# quadstep-v020.net
KiCad netlist of a schematic drawn in EAGLE
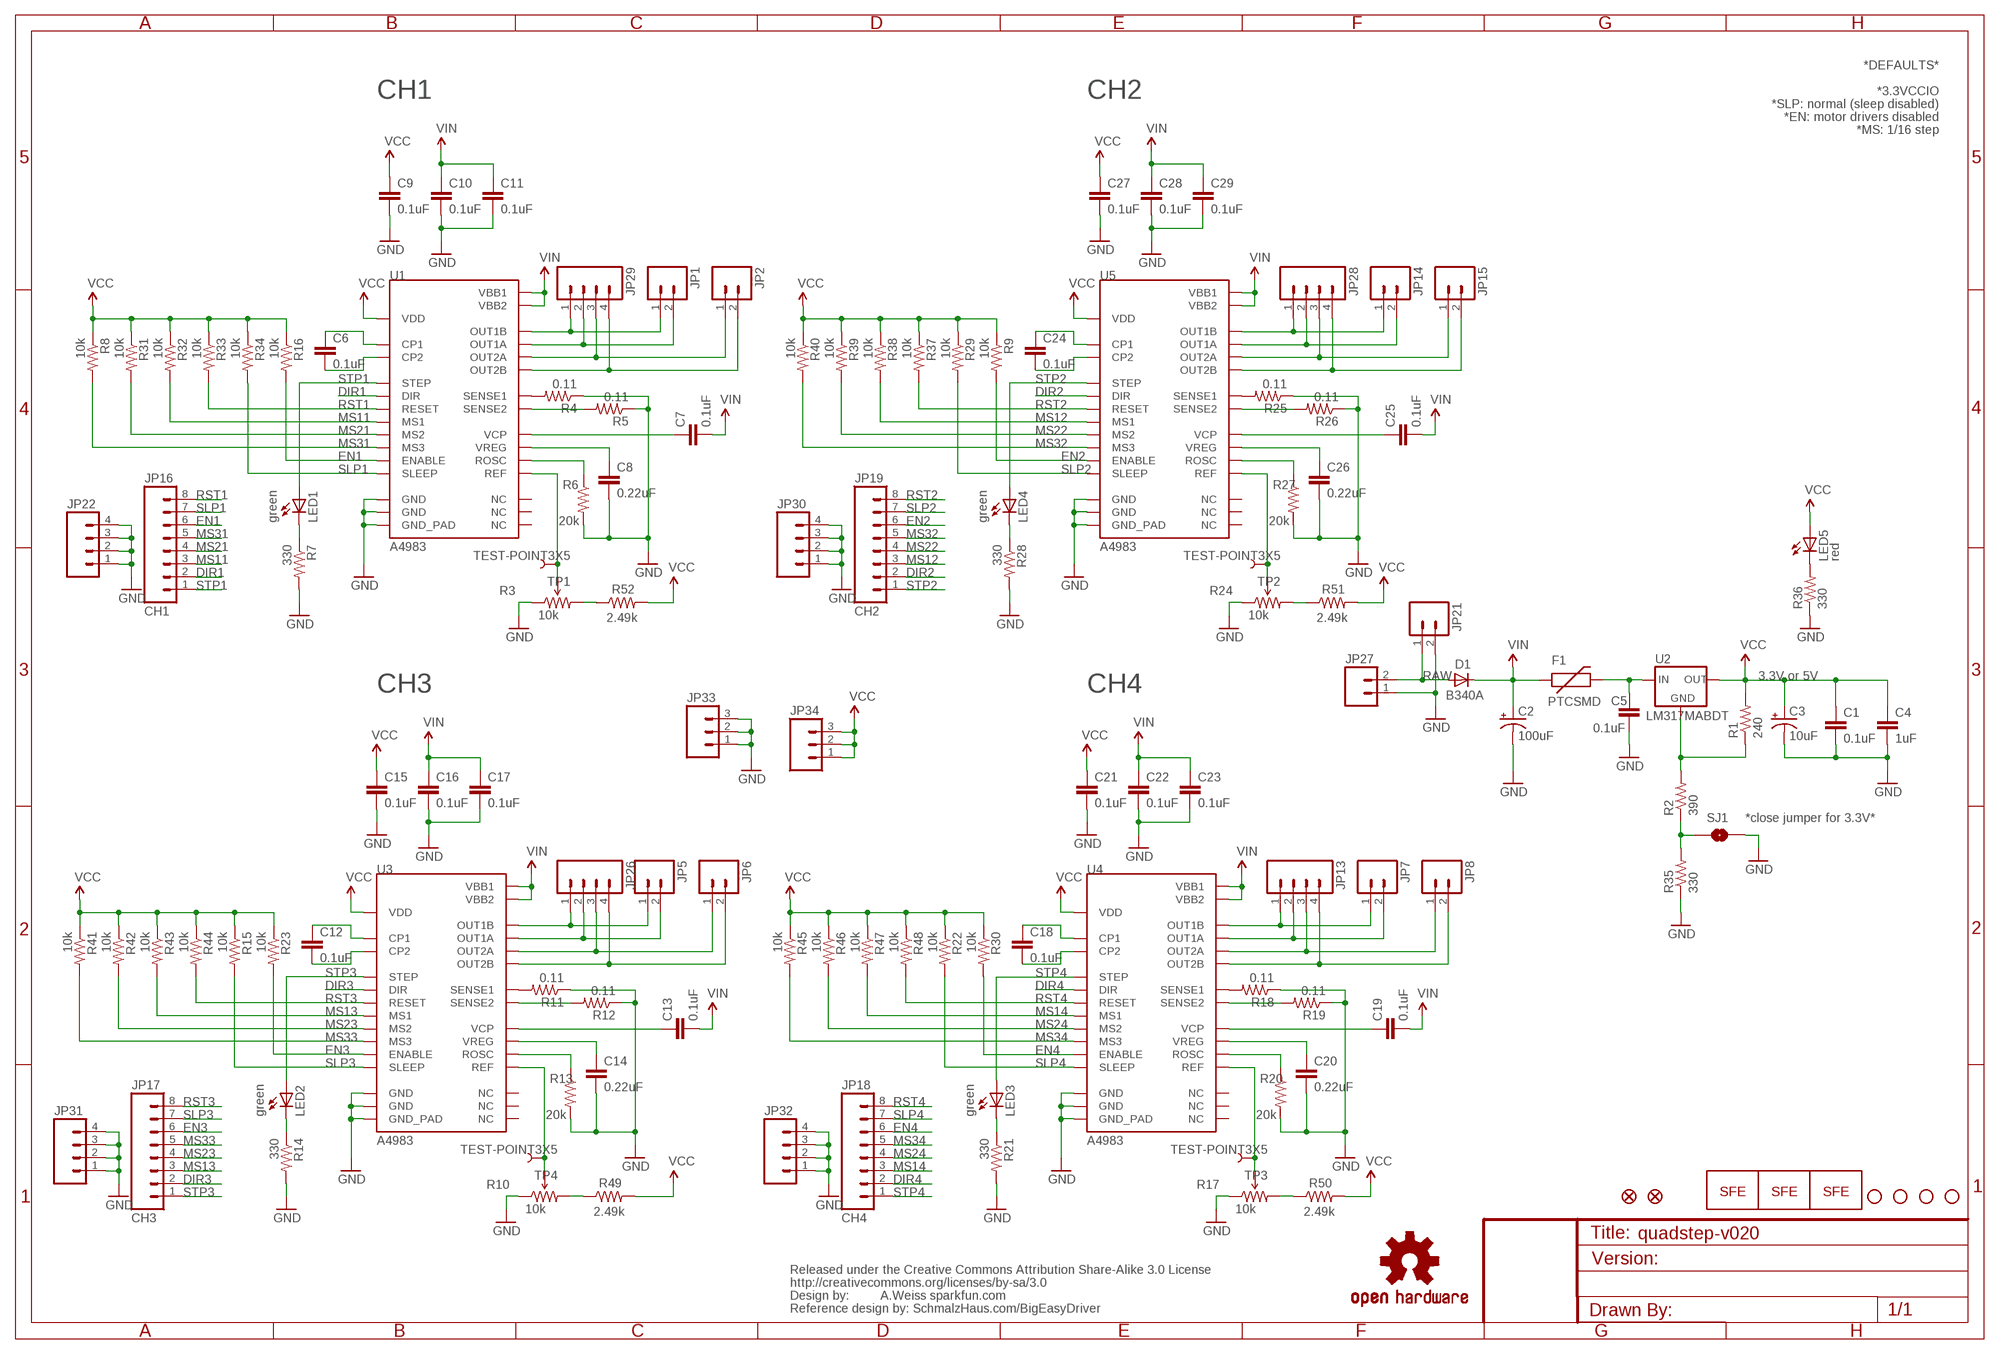
[diagram p0: schematic, sheet 1]

(export (version "E")
  (design (tool "Eeschema 10.0.6"))
  (components
    (comp (ref "C1")
      (value "0.1uF")
      (footprint "eagle-import:0402-CAP")
      (libsource (lib "eagle-import") (part "CAP0402-CAP"))
    )
    (comp (ref "C2")
      (value "100uF")
      (footprint "eagle-import:PANASONIC_G")
      (libsource (lib "eagle-import") (part "CAP_POLG"))
    )
    (comp (ref "C3")
      (value "10uF")
      (footprint "eagle-import:EIA3216")
      (libsource (lib "eagle-import") (part "CAP_POL1206"))
    )
    (comp (ref "C4")
      (value "1uF")
      (footprint "eagle-import:0805")
      (libsource (lib "eagle-import") (part "CAP0805"))
    )
    (comp (ref "C5")
      (value "0.1uF")
      (footprint "eagle-import:0402-CAP")
      (libsource (lib "eagle-import") (part "CAP0402-CAP"))
    )
    (comp (ref "C6")
      (value "0.1uF")
      (footprint "eagle-import:0402-CAP")
      (libsource (lib "eagle-import") (part "CAP0402-CAP"))
    )
    (comp (ref "C7")
      (value "0.1uF")
      (footprint "eagle-import:0402-CAP")
      (libsource (lib "eagle-import") (part "CAP0402-CAP"))
    )
    (comp (ref "C8")
      (value "0.22uF")
      (footprint "eagle-import:0402-CAP")
      (libsource (lib "eagle-import") (part "CAP0402-CAP"))
    )
    (comp (ref "C9")
      (value "0.1uF")
      (footprint "eagle-import:0402-CAP")
      (libsource (lib "eagle-import") (part "CAP0402-CAP"))
    )
    (comp (ref "C10")
      (value "0.1uF")
      (footprint "eagle-import:0402-CAP")
      (libsource (lib "eagle-import") (part "CAP0402-CAP"))
    )
    (comp (ref "C11")
      (value "0.1uF")
      (footprint "eagle-import:0402-CAP")
      (libsource (lib "eagle-import") (part "CAP0402-CAP"))
    )
    (comp (ref "C12")
      (value "0.1uF")
      (footprint "eagle-import:0402-CAP")
      (libsource (lib "eagle-import") (part "CAP0402-CAP"))
    )
    (comp (ref "C13")
      (value "0.1uF")
      (footprint "eagle-import:0402-CAP")
      (libsource (lib "eagle-import") (part "CAP0402-CAP"))
    )
    (comp (ref "C14")
      (value "0.22uF")
      (footprint "eagle-import:0402-CAP")
      (libsource (lib "eagle-import") (part "CAP0402-CAP"))
    )
    (comp (ref "C15")
      (value "0.1uF")
      (footprint "eagle-import:0402-CAP")
      (libsource (lib "eagle-import") (part "CAP0402-CAP"))
    )
    (comp (ref "C16")
      (value "0.1uF")
      (footprint "eagle-import:0402-CAP")
      (libsource (lib "eagle-import") (part "CAP0402-CAP"))
    )
    (comp (ref "C17")
      (value "0.1uF")
      (footprint "eagle-import:0402-CAP")
      (libsource (lib "eagle-import") (part "CAP0402-CAP"))
    )
    (comp (ref "C18")
      (value "0.1uF")
      (footprint "eagle-import:0402-CAP")
      (libsource (lib "eagle-import") (part "CAP0402-CAP"))
    )
    (comp (ref "C19")
      (value "0.1uF")
      (footprint "eagle-import:0402-CAP")
      (libsource (lib "eagle-import") (part "CAP0402-CAP"))
    )
    (comp (ref "C20")
      (value "0.22uF")
      (footprint "eagle-import:0402-CAP")
      (libsource (lib "eagle-import") (part "CAP0402-CAP"))
    )
    (comp (ref "C21")
      (value "0.1uF")
      (footprint "eagle-import:0402-CAP")
      (libsource (lib "eagle-import") (part "CAP0402-CAP"))
    )
    (comp (ref "C22")
      (value "0.1uF")
      (footprint "eagle-import:0402-CAP")
      (libsource (lib "eagle-import") (part "CAP0402-CAP"))
    )
    (comp (ref "C23")
      (value "0.1uF")
      (footprint "eagle-import:0402-CAP")
      (libsource (lib "eagle-import") (part "CAP0402-CAP"))
    )
    (comp (ref "C24")
      (value "0.1uF")
      (footprint "eagle-import:0402-CAP")
      (libsource (lib "eagle-import") (part "CAP0402-CAP"))
    )
    (comp (ref "C25")
      (value "0.1uF")
      (footprint "eagle-import:0402-CAP")
      (libsource (lib "eagle-import") (part "CAP0402-CAP"))
    )
    (comp (ref "C26")
      (value "0.22uF")
      (footprint "eagle-import:0402-CAP")
      (libsource (lib "eagle-import") (part "CAP0402-CAP"))
    )
    (comp (ref "C27")
      (value "0.1uF")
      (footprint "eagle-import:0402-CAP")
      (libsource (lib "eagle-import") (part "CAP0402-CAP"))
    )
    (comp (ref "C28")
      (value "0.1uF")
      (footprint "eagle-import:0402-CAP")
      (libsource (lib "eagle-import") (part "CAP0402-CAP"))
    )
    (comp (ref "C29")
      (value "0.1uF")
      (footprint "eagle-import:0402-CAP")
      (libsource (lib "eagle-import") (part "CAP0402-CAP"))
    )
    (comp (ref "CC_TEXT1")
      (value "CREATIVE_COMMONS")
      (footprint "eagle-import:CREATIVE_COMMONS")
      (libsource (lib "eagle-import") (part "CREATIVE_COMMONS"))
    )
    (comp (ref "D1")
      (value "B340A")
      (footprint "eagle-import:SMA-DIODE")
      (libsource (lib "eagle-import") (part "DIODESMA"))
    )
    (comp (ref "F1")
      (value "PTCSMD")
      (footprint "eagle-import:PTC-1206")
      (libsource (lib "eagle-import") (part "PTCSMD"))
    )
    (comp (ref "JP1")
      (value "M023.5MM_LOCK")
      (footprint "eagle-import:SCREWTERMINAL-3.5MM-2_LOCK")
      (libsource (lib "eagle-import") (part "M023.5MM_LOCK"))
    )
    (comp (ref "JP2")
      (value "M023.5MM_LOCK")
      (footprint "eagle-import:SCREWTERMINAL-3.5MM-2_LOCK")
      (libsource (lib "eagle-import") (part "M023.5MM_LOCK"))
    )
    (comp (ref "JP5")
      (value "M023.5MM_LOCK")
      (footprint "eagle-import:SCREWTERMINAL-3.5MM-2_LOCK")
      (libsource (lib "eagle-import") (part "M023.5MM_LOCK"))
    )
    (comp (ref "JP6")
      (value "M023.5MM_LOCK")
      (footprint "eagle-import:SCREWTERMINAL-3.5MM-2_LOCK")
      (libsource (lib "eagle-import") (part "M023.5MM_LOCK"))
    )
    (comp (ref "JP7")
      (value "M023.5MM_LOCK")
      (footprint "eagle-import:SCREWTERMINAL-3.5MM-2_LOCK")
      (libsource (lib "eagle-import") (part "M023.5MM_LOCK"))
    )
    (comp (ref "JP8")
      (value "M023.5MM_LOCK")
      (footprint "eagle-import:SCREWTERMINAL-3.5MM-2_LOCK")
      (libsource (lib "eagle-import") (part "M023.5MM_LOCK"))
    )
    (comp (ref "JP9")
      (value "STAND-OFF")
      (footprint "eagle-import:STAND-OFF")
      (libsource (lib "eagle-import") (part "STAND-OFF"))
    )
    (comp (ref "JP10")
      (value "STAND-OFF")
      (footprint "eagle-import:STAND-OFF")
      (libsource (lib "eagle-import") (part "STAND-OFF"))
    )
    (comp (ref "JP11")
      (value "STAND-OFF")
      (footprint "eagle-import:STAND-OFF")
      (libsource (lib "eagle-import") (part "STAND-OFF"))
    )
    (comp (ref "JP12")
      (value "STAND-OFF")
      (footprint "eagle-import:STAND-OFF")
      (libsource (lib "eagle-import") (part "STAND-OFF"))
    )
    (comp (ref "JP13")
      (value "M04PTH")
      (footprint "eagle-import:1X04")
      (libsource (lib "eagle-import") (part "M04PTH"))
    )
    (comp (ref "JP14")
      (value "M023.5MM_LOCK")
      (footprint "eagle-import:SCREWTERMINAL-3.5MM-2_LOCK")
      (libsource (lib "eagle-import") (part "M023.5MM_LOCK"))
    )
    (comp (ref "JP15")
      (value "M023.5MM_LOCK")
      (footprint "eagle-import:SCREWTERMINAL-3.5MM-2_LOCK")
      (libsource (lib "eagle-import") (part "M023.5MM_LOCK"))
    )
    (comp (ref "JP16")
      (value "CH1")
      (footprint "eagle-import:1X08")
      (libsource (lib "eagle-import") (part "M08"))
    )
    (comp (ref "JP17")
      (value "CH3")
      (footprint "eagle-import:1X08")
      (libsource (lib "eagle-import") (part "M08"))
    )
    (comp (ref "JP18")
      (value "CH4")
      (footprint "eagle-import:1X08")
      (libsource (lib "eagle-import") (part "M08"))
    )
    (comp (ref "JP19")
      (value "CH2")
      (footprint "eagle-import:1X08")
      (libsource (lib "eagle-import") (part "M08"))
    )
    (comp (ref "JP20")
      (value "LOGO-SFENEW")
      (footprint "eagle-import:SFE-NEW-WEBLOGO")
      (libsource (lib "eagle-import") (part "LOGO-SFENEW"))
    )
    (comp (ref "JP21")
      (value "M025MM")
      (footprint "eagle-import:SCREWTERMINAL-5MM-2")
      (libsource (lib "eagle-import") (part "M025MM"))
    )
    (comp (ref "JP22")
      (value "M04PTH")
      (footprint "eagle-import:1X04")
      (libsource (lib "eagle-import") (part "M04PTH"))
    )
    (comp (ref "JP23")
      (value "LOGO-SFESK")
      (footprint "eagle-import:SFE-LOGO-FLAME")
      (libsource (lib "eagle-import") (part "LOGO-SFESK"))
    )
    (comp (ref "JP24")
      (value "FIDUCIAL1X2")
      (footprint "eagle-import:FIDUCIAL-1X2")
      (libsource (lib "eagle-import") (part "FIDUCIAL1X2"))
    )
    (comp (ref "JP25")
      (value "FIDUCIAL1X2")
      (footprint "eagle-import:FIDUCIAL-1X2")
      (libsource (lib "eagle-import") (part "FIDUCIAL1X2"))
    )
    (comp (ref "JP26")
      (value "M04PTH")
      (footprint "eagle-import:1X04")
      (libsource (lib "eagle-import") (part "M04PTH"))
    )
    (comp (ref "JP27")
      (value "M02PTH")
      (footprint "eagle-import:1X02")
      (libsource (lib "eagle-import") (part "SparkFun-Connectors_M02PTH"))
    )
    (comp (ref "JP28")
      (value "M04PTH")
      (footprint "eagle-import:1X04")
      (libsource (lib "eagle-import") (part "M04PTH"))
    )
    (comp (ref "JP29")
      (value "M04PTH")
      (footprint "eagle-import:1X04")
      (libsource (lib "eagle-import") (part "M04PTH"))
    )
    (comp (ref "JP30")
      (value "M04PTH")
      (footprint "eagle-import:1X04")
      (libsource (lib "eagle-import") (part "M04PTH"))
    )
    (comp (ref "JP31")
      (value "M04PTH")
      (footprint "eagle-import:1X04")
      (libsource (lib "eagle-import") (part "M04PTH"))
    )
    (comp (ref "JP32")
      (value "M04PTH")
      (footprint "eagle-import:1X04")
      (libsource (lib "eagle-import") (part "M04PTH"))
    )
    (comp (ref "JP33")
      (value "M03PTH")
      (footprint "eagle-import:1X03")
      (libsource (lib "eagle-import") (part "M03PTH"))
    )
    (comp (ref "JP34")
      (value "M03PTH")
      (footprint "eagle-import:1X03")
      (libsource (lib "eagle-import") (part "M03PTH"))
    )
    (comp (ref "LED1")
      (value "green")
      (footprint "eagle-import:LED-0603")
      (libsource (lib "eagle-import") (part "LED0603"))
    )
    (comp (ref "LED2")
      (value "green")
      (footprint "eagle-import:LED-0603")
      (libsource (lib "eagle-import") (part "LED0603"))
    )
    (comp (ref "LED3")
      (value "green")
      (footprint "eagle-import:LED-0603")
      (libsource (lib "eagle-import") (part "LED0603"))
    )
    (comp (ref "LED4")
      (value "green")
      (footprint "eagle-import:LED-0603")
      (libsource (lib "eagle-import") (part "LED0603"))
    )
    (comp (ref "LED5")
      (value "red")
      (footprint "eagle-import:LED-0603")
      (libsource (lib "eagle-import") (part "LED0603"))
    )
    (comp (ref "LOGO1")
      (value "LOGO-SFENW2")
      (footprint "eagle-import:SFE-NEW-WEB")
      (libsource (lib "eagle-import") (part "SparkFun-Aesthetics_LOGO-SFENW2"))
    )
    (comp (ref "R1")
      (value "240")
      (footprint "eagle-import:0402-RES")
      (libsource (lib "eagle-import") (part "RESISTOR0402-RES"))
    )
    (comp (ref "R2")
      (value "390")
      (footprint "eagle-import:0402-RES")
      (libsource (lib "eagle-import") (part "RESISTOR0402-RES"))
    )
    (comp (ref "R3")
      (value "10k")
      (footprint "eagle-import:TRIMPOT-3MM")
      (libsource (lib "eagle-import") (part "TRIMPOTSMD"))
    )
    (comp (ref "R4")
      (value "0.11")
      (footprint "eagle-import:R2010")
      (libsource (lib "eagle-import") (part "RESISTOR2010"))
    )
    (comp (ref "R5")
      (value "0.11")
      (footprint "eagle-import:R2010")
      (libsource (lib "eagle-import") (part "RESISTOR2010"))
    )
    (comp (ref "R6")
      (value "20k")
      (footprint "eagle-import:0402-RES")
      (libsource (lib "eagle-import") (part "RESISTOR0402-RES"))
    )
    (comp (ref "R7")
      (value "330")
      (footprint "eagle-import:0402-RES")
      (libsource (lib "eagle-import") (part "RESISTOR0402-RES"))
    )
    (comp (ref "R8")
      (value "10k")
      (footprint "eagle-import:0402-RES")
      (libsource (lib "eagle-import") (part "RESISTOR0402-RES"))
    )
    (comp (ref "R9")
      (value "10k")
      (footprint "eagle-import:0402-RES")
      (libsource (lib "eagle-import") (part "RESISTOR0402-RES"))
    )
    (comp (ref "R10")
      (value "10k")
      (footprint "eagle-import:TRIMPOT-3MM")
      (libsource (lib "eagle-import") (part "TRIMPOTSMD"))
    )
    (comp (ref "R11")
      (value "0.11")
      (footprint "eagle-import:R2010")
      (libsource (lib "eagle-import") (part "RESISTOR2010"))
    )
    (comp (ref "R12")
      (value "0.11")
      (footprint "eagle-import:R2010")
      (libsource (lib "eagle-import") (part "RESISTOR2010"))
    )
    (comp (ref "R13")
      (value "20k")
      (footprint "eagle-import:0402-RES")
      (libsource (lib "eagle-import") (part "RESISTOR0402-RES"))
    )
    (comp (ref "R14")
      (value "330")
      (footprint "eagle-import:0402-RES")
      (libsource (lib "eagle-import") (part "RESISTOR0402-RES"))
    )
    (comp (ref "R15")
      (value "10k")
      (footprint "eagle-import:0402-RES")
      (libsource (lib "eagle-import") (part "RESISTOR0402-RES"))
    )
    (comp (ref "R16")
      (value "10k")
      (footprint "eagle-import:0402-RES")
      (libsource (lib "eagle-import") (part "RESISTOR0402-RES"))
    )
    (comp (ref "R17")
      (value "10k")
      (footprint "eagle-import:TRIMPOT-3MM")
      (libsource (lib "eagle-import") (part "TRIMPOTSMD"))
    )
    (comp (ref "R18")
      (value "0.11")
      (footprint "eagle-import:R2010")
      (libsource (lib "eagle-import") (part "RESISTOR2010"))
    )
    (comp (ref "R19")
      (value "0.11")
      (footprint "eagle-import:R2010")
      (libsource (lib "eagle-import") (part "RESISTOR2010"))
    )
    (comp (ref "R20")
      (value "20k")
      (footprint "eagle-import:0402-RES")
      (libsource (lib "eagle-import") (part "RESISTOR0402-RES"))
    )
    (comp (ref "R21")
      (value "330")
      (footprint "eagle-import:0402-RES")
      (libsource (lib "eagle-import") (part "RESISTOR0402-RES"))
    )
    (comp (ref "R22")
      (value "10k")
      (footprint "eagle-import:0402-RES")
      (libsource (lib "eagle-import") (part "RESISTOR0402-RES"))
    )
    (comp (ref "R23")
      (value "10k")
      (footprint "eagle-import:0402-RES")
      (libsource (lib "eagle-import") (part "RESISTOR0402-RES"))
    )
    (comp (ref "R24")
      (value "10k")
      (footprint "eagle-import:TRIMPOT-3MM")
      (libsource (lib "eagle-import") (part "TRIMPOTSMD"))
    )
    (comp (ref "R25")
      (value "0.11")
      (footprint "eagle-import:R2010")
      (libsource (lib "eagle-import") (part "RESISTOR2010"))
    )
    (comp (ref "R26")
      (value "0.11")
      (footprint "eagle-import:R2010")
      (libsource (lib "eagle-import") (part "RESISTOR2010"))
    )
    (comp (ref "R27")
      (value "20k")
      (footprint "eagle-import:0402-RES")
      (libsource (lib "eagle-import") (part "RESISTOR0402-RES"))
    )
    (comp (ref "R28")
      (value "330")
      (footprint "eagle-import:0402-RES")
      (libsource (lib "eagle-import") (part "RESISTOR0402-RES"))
    )
    (comp (ref "R29")
      (value "10k")
      (footprint "eagle-import:0402-RES")
      (libsource (lib "eagle-import") (part "RESISTOR0402-RES"))
    )
    (comp (ref "R30")
      (value "10k")
      (footprint "eagle-import:0402-RES")
      (libsource (lib "eagle-import") (part "RESISTOR0402-RES"))
    )
    (comp (ref "R31")
      (value "10k")
      (footprint "eagle-import:0402-RES")
      (libsource (lib "eagle-import") (part "RESISTOR0402-RES"))
    )
    (comp (ref "R32")
      (value "10k")
      (footprint "eagle-import:0402-RES")
      (libsource (lib "eagle-import") (part "RESISTOR0402-RES"))
    )
    (comp (ref "R33")
      (value "10k")
      (footprint "eagle-import:0402-RES")
      (libsource (lib "eagle-import") (part "RESISTOR0402-RES"))
    )
    (comp (ref "R34")
      (value "10k")
      (footprint "eagle-import:0402-RES")
      (libsource (lib "eagle-import") (part "RESISTOR0402-RES"))
    )
    (comp (ref "R35")
      (value "330")
      (footprint "eagle-import:0402-RES")
      (libsource (lib "eagle-import") (part "RESISTOR0402-RES"))
    )
    (comp (ref "R36")
      (value "330")
      (footprint "eagle-import:0402-RES")
      (libsource (lib "eagle-import") (part "RESISTOR0402-RES"))
    )
    (comp (ref "R37")
      (value "10k")
      (footprint "eagle-import:0402-RES")
      (libsource (lib "eagle-import") (part "RESISTOR0402-RES"))
    )
    (comp (ref "R38")
      (value "10k")
      (footprint "eagle-import:0402-RES")
      (libsource (lib "eagle-import") (part "RESISTOR0402-RES"))
    )
    (comp (ref "R39")
      (value "10k")
      (footprint "eagle-import:0402-RES")
      (libsource (lib "eagle-import") (part "RESISTOR0402-RES"))
    )
    (comp (ref "R40")
      (value "10k")
      (footprint "eagle-import:0402-RES")
      (libsource (lib "eagle-import") (part "RESISTOR0402-RES"))
    )
    (comp (ref "R41")
      (value "10k")
      (footprint "eagle-import:0402-RES")
      (libsource (lib "eagle-import") (part "RESISTOR0402-RES"))
    )
    (comp (ref "R42")
      (value "10k")
      (footprint "eagle-import:0402-RES")
      (libsource (lib "eagle-import") (part "RESISTOR0402-RES"))
    )
    (comp (ref "R43")
      (value "10k")
      (footprint "eagle-import:0402-RES")
      (libsource (lib "eagle-import") (part "RESISTOR0402-RES"))
    )
    (comp (ref "R44")
      (value "10k")
      (footprint "eagle-import:0402-RES")
      (libsource (lib "eagle-import") (part "RESISTOR0402-RES"))
    )
    (comp (ref "R45")
      (value "10k")
      (footprint "eagle-import:0402-RES")
      (libsource (lib "eagle-import") (part "RESISTOR0402-RES"))
    )
    (comp (ref "R46")
      (value "10k")
      (footprint "eagle-import:0402-RES")
      (libsource (lib "eagle-import") (part "RESISTOR0402-RES"))
    )
    (comp (ref "R47")
      (value "10k")
      (footprint "eagle-import:0402-RES")
      (libsource (lib "eagle-import") (part "RESISTOR0402-RES"))
    )
    (comp (ref "R48")
      (value "10k")
      (footprint "eagle-import:0402-RES")
      (libsource (lib "eagle-import") (part "RESISTOR0402-RES"))
    )
    (comp (ref "R49")
      (value "2.49k")
      (footprint "eagle-import:0402-RES")
      (libsource (lib "eagle-import") (part "RESISTOR0402-RES"))
    )
    (comp (ref "R50")
      (value "2.49k")
      (footprint "eagle-import:0402-RES")
      (libsource (lib "eagle-import") (part "RESISTOR0402-RES"))
    )
    (comp (ref "R51")
      (value "2.49k")
      (footprint "eagle-import:0402-RES")
      (libsource (lib "eagle-import") (part "RESISTOR0402-RES"))
    )
    (comp (ref "R52")
      (value "2.49k")
      (footprint "eagle-import:0402-RES")
      (libsource (lib "eagle-import") (part "RESISTOR0402-RES"))
    )
    (comp (ref "SJ1")
      (value "SOLDERJUMPERNO")
      (footprint "eagle-import:SJ_2S-NO")
      (libsource (lib "eagle-import") (part "SOLDERJUMPERNO"))
    )
    (comp (ref "TP1")
      (value "TEST-POINT3X5")
      (footprint "eagle-import:PAD.03X.05")
      (libsource (lib "eagle-import") (part "TEST-POINT3X5"))
    )
    (comp (ref "TP2")
      (value "TEST-POINT3X5")
      (footprint "eagle-import:PAD.03X.05")
      (libsource (lib "eagle-import") (part "TEST-POINT3X5"))
    )
    (comp (ref "TP3")
      (value "TEST-POINT3X5")
      (footprint "eagle-import:PAD.03X.05")
      (libsource (lib "eagle-import") (part "TEST-POINT3X5"))
    )
    (comp (ref "TP4")
      (value "TEST-POINT3X5")
      (footprint "eagle-import:PAD.03X.05")
      (libsource (lib "eagle-import") (part "TEST-POINT3X5"))
    )
    (comp (ref "U$1")
      (value "OSHW-LOGOS")
      (footprint "eagle-import:OSHW-LOGO-S")
      (libsource (lib "eagle-import") (part "OSHW-LOGOS"))
    )
    (comp (ref "U1")
      (value "A4983")
      (footprint "eagle-import:QFN-28-5MM")
      (libsource (lib "eagle-import") (part "A4983"))
    )
    (comp (ref "U2")
      (value "LM317MABDT")
      (footprint "eagle-import:DPAK")
      (libsource (lib "eagle-import") (part "V_REG_MC33269DT"))
    )
    (comp (ref "U3")
      (value "A4983")
      (footprint "eagle-import:QFN-28-5MM")
      (libsource (lib "eagle-import") (part "A4983"))
    )
    (comp (ref "U4")
      (value "A4983")
      (footprint "eagle-import:QFN-28-5MM")
      (libsource (lib "eagle-import") (part "A4983"))
    )
    (comp (ref "U5")
      (value "A4983")
      (footprint "eagle-import:QFN-28-5MM")
      (libsource (lib "eagle-import") (part "A4983"))
    )
  )
  (nets
    (net (code "1") (name "/DIR1") (class "Default")
      (node (ref "JP16") (pin "2") (pinfunction "2_2") (pintype "passive"))
      (node (ref "U1") (pin "P$19") (pinfunction "DIR_P$19") (pintype "input"))
    )
    (net (code "2") (name "/DIR2") (class "Default")
      (node (ref "JP19") (pin "2") (pinfunction "2_2") (pintype "passive"))
      (node (ref "U5") (pin "P$19") (pinfunction "DIR_P$19") (pintype "input"))
    )
    (net (code "3") (name "/DIR3") (class "Default")
      (node (ref "JP17") (pin "2") (pinfunction "2_2") (pintype "passive"))
      (node (ref "U3") (pin "P$19") (pinfunction "DIR_P$19") (pintype "input"))
    )
    (net (code "4") (name "/DIR4") (class "Default")
      (node (ref "JP18") (pin "2") (pinfunction "2_2") (pintype "passive"))
      (node (ref "U4") (pin "P$19") (pinfunction "DIR_P$19") (pintype "input"))
    )
    (net (code "5") (name "/EN1") (class "Default")
      (node (ref "JP16") (pin "6") (pinfunction "6_6") (pintype "passive"))
      (node (ref "R16") (pin "2") (pinfunction "2_2") (pintype "passive"))
      (node (ref "U1") (pin "P$2") (pinfunction "ENABLE_P$2") (pintype "input"))
    )
    (net (code "6") (name "/EN2") (class "Default")
      (node (ref "JP19") (pin "6") (pinfunction "6_6") (pintype "passive"))
      (node (ref "R9") (pin "2") (pinfunction "2_2") (pintype "passive"))
      (node (ref "U5") (pin "P$2") (pinfunction "ENABLE_P$2") (pintype "input"))
    )
    (net (code "7") (name "/EN3") (class "Default")
      (node (ref "JP17") (pin "6") (pinfunction "6_6") (pintype "passive"))
      (node (ref "R23") (pin "2") (pinfunction "2_2") (pintype "passive"))
      (node (ref "U3") (pin "P$2") (pinfunction "ENABLE_P$2") (pintype "input"))
    )
    (net (code "8") (name "/EN4") (class "Default")
      (node (ref "JP18") (pin "6") (pinfunction "6_6") (pintype "passive"))
      (node (ref "R30") (pin "2") (pinfunction "2_2") (pintype "passive"))
      (node (ref "U4") (pin "P$2") (pinfunction "ENABLE_P$2") (pintype "input"))
    )
    (net (code "9") (name "/MS11") (class "Default")
      (node (ref "JP16") (pin "3") (pinfunction "3_3") (pintype "passive"))
      (node (ref "R32") (pin "2") (pinfunction "2_2") (pintype "passive"))
      (node (ref "U1") (pin "P$9") (pinfunction "MS1_P$9") (pintype "input"))
    )
    (net (code "10") (name "/MS12") (class "Default")
      (node (ref "JP19") (pin "3") (pinfunction "3_3") (pintype "passive"))
      (node (ref "R38") (pin "2") (pinfunction "2_2") (pintype "passive"))
      (node (ref "U5") (pin "P$9") (pinfunction "MS1_P$9") (pintype "input"))
    )
    (net (code "11") (name "/MS13") (class "Default")
      (node (ref "JP17") (pin "3") (pinfunction "3_3") (pintype "passive"))
      (node (ref "R43") (pin "2") (pinfunction "2_2") (pintype "passive"))
      (node (ref "U3") (pin "P$9") (pinfunction "MS1_P$9") (pintype "input"))
    )
    (net (code "12") (name "/MS14") (class "Default")
      (node (ref "JP18") (pin "3") (pinfunction "3_3") (pintype "passive"))
      (node (ref "R47") (pin "2") (pinfunction "2_2") (pintype "passive"))
      (node (ref "U4") (pin "P$9") (pinfunction "MS1_P$9") (pintype "input"))
    )
    (net (code "13") (name "/MS21") (class "Default")
      (node (ref "JP16") (pin "4") (pinfunction "4_4") (pintype "passive"))
      (node (ref "R31") (pin "2") (pinfunction "2_2") (pintype "passive"))
      (node (ref "U1") (pin "P$10") (pinfunction "MS2_P$10") (pintype "input"))
    )
    (net (code "14") (name "/MS22") (class "Default")
      (node (ref "JP19") (pin "4") (pinfunction "4_4") (pintype "passive"))
      (node (ref "R39") (pin "2") (pinfunction "2_2") (pintype "passive"))
      (node (ref "U5") (pin "P$10") (pinfunction "MS2_P$10") (pintype "input"))
    )
    (net (code "15") (name "/MS23") (class "Default")
      (node (ref "JP17") (pin "4") (pinfunction "4_4") (pintype "passive"))
      (node (ref "R42") (pin "2") (pinfunction "2_2") (pintype "passive"))
      (node (ref "U3") (pin "P$10") (pinfunction "MS2_P$10") (pintype "input"))
    )
    (net (code "16") (name "/MS24") (class "Default")
      (node (ref "JP18") (pin "4") (pinfunction "4_4") (pintype "passive"))
      (node (ref "R46") (pin "2") (pinfunction "2_2") (pintype "passive"))
      (node (ref "U4") (pin "P$10") (pinfunction "MS2_P$10") (pintype "input"))
    )
    (net (code "17") (name "/MS31") (class "Default")
      (node (ref "JP16") (pin "5") (pinfunction "5_5") (pintype "passive"))
      (node (ref "R8") (pin "2") (pinfunction "2_2") (pintype "passive"))
      (node (ref "U1") (pin "P$11") (pinfunction "MS3_P$11") (pintype "input"))
    )
    (net (code "18") (name "/MS32") (class "Default")
      (node (ref "JP19") (pin "5") (pinfunction "5_5") (pintype "passive"))
      (node (ref "R40") (pin "2") (pinfunction "2_2") (pintype "passive"))
      (node (ref "U5") (pin "P$11") (pinfunction "MS3_P$11") (pintype "input"))
    )
    (net (code "19") (name "/MS33") (class "Default")
      (node (ref "JP17") (pin "5") (pinfunction "5_5") (pintype "passive"))
      (node (ref "R41") (pin "2") (pinfunction "2_2") (pintype "passive"))
      (node (ref "U3") (pin "P$11") (pinfunction "MS3_P$11") (pintype "input"))
    )
    (net (code "20") (name "/MS34") (class "Default")
      (node (ref "JP18") (pin "5") (pinfunction "5_5") (pintype "passive"))
      (node (ref "R45") (pin "2") (pinfunction "2_2") (pintype "passive"))
      (node (ref "U4") (pin "P$11") (pinfunction "MS3_P$11") (pintype "input"))
    )
    (net (code "21") (name "/RAW") (class "Default")
      (node (ref "D1") (pin "A") (pinfunction "A_A") (pintype "passive"))
      (node (ref "JP21") (pin "1") (pinfunction "1_1") (pintype "passive"))
      (node (ref "JP27") (pin "2") (pinfunction "2_2") (pintype "passive"))
    )
    (net (code "22") (name "/RST1") (class "Default")
      (node (ref "JP16") (pin "8") (pinfunction "8_8") (pintype "passive"))
      (node (ref "R33") (pin "2") (pinfunction "2_2") (pintype "passive"))
      (node (ref "U1") (pin "P$12") (pinfunction "RESET_P$12") (pintype "input"))
    )
    (net (code "23") (name "/RST2") (class "Default")
      (node (ref "JP19") (pin "8") (pinfunction "8_8") (pintype "passive"))
      (node (ref "R37") (pin "2") (pinfunction "2_2") (pintype "passive"))
      (node (ref "U5") (pin "P$12") (pinfunction "RESET_P$12") (pintype "input"))
    )
    (net (code "24") (name "/RST3") (class "Default")
      (node (ref "JP17") (pin "8") (pinfunction "8_8") (pintype "passive"))
      (node (ref "R44") (pin "2") (pinfunction "2_2") (pintype "passive"))
      (node (ref "U3") (pin "P$12") (pinfunction "RESET_P$12") (pintype "input"))
    )
    (net (code "25") (name "/RST4") (class "Default")
      (node (ref "JP18") (pin "8") (pinfunction "8_8") (pintype "passive"))
      (node (ref "R48") (pin "2") (pinfunction "2_2") (pintype "passive"))
      (node (ref "U4") (pin "P$12") (pinfunction "RESET_P$12") (pintype "input"))
    )
    (net (code "26") (name "/SLP1") (class "Default")
      (node (ref "JP16") (pin "7") (pinfunction "7_7") (pintype "passive"))
      (node (ref "R34") (pin "2") (pinfunction "2_2") (pintype "passive"))
      (node (ref "U1") (pin "P$14") (pinfunction "SLEEP_P$14") (pintype "input"))
    )
    (net (code "27") (name "/SLP2") (class "Default")
      (node (ref "JP19") (pin "7") (pinfunction "7_7") (pintype "passive"))
      (node (ref "R29") (pin "2") (pinfunction "2_2") (pintype "passive"))
      (node (ref "U5") (pin "P$14") (pinfunction "SLEEP_P$14") (pintype "input"))
    )
    (net (code "28") (name "/SLP3") (class "Default")
      (node (ref "JP17") (pin "7") (pinfunction "7_7") (pintype "passive"))
      (node (ref "R15") (pin "2") (pinfunction "2_2") (pintype "passive"))
      (node (ref "U3") (pin "P$14") (pinfunction "SLEEP_P$14") (pintype "input"))
    )
    (net (code "29") (name "/SLP4") (class "Default")
      (node (ref "JP18") (pin "7") (pinfunction "7_7") (pintype "passive"))
      (node (ref "R22") (pin "2") (pinfunction "2_2") (pintype "passive"))
      (node (ref "U4") (pin "P$14") (pinfunction "SLEEP_P$14") (pintype "input"))
    )
    (net (code "30") (name "/STP1") (class "Default")
      (node (ref "JP16") (pin "1") (pinfunction "1_1") (pintype "passive"))
      (node (ref "LED1") (pin "A") (pinfunction "A_A") (pintype "passive"))
      (node (ref "U1") (pin "P$16") (pinfunction "STEP_P$16") (pintype "input"))
    )
    (net (code "31") (name "/STP2") (class "Default")
      (node (ref "JP19") (pin "1") (pinfunction "1_1") (pintype "passive"))
      (node (ref "LED4") (pin "A") (pinfunction "A_A") (pintype "passive"))
      (node (ref "U5") (pin "P$16") (pinfunction "STEP_P$16") (pintype "input"))
    )
    (net (code "32") (name "/STP3") (class "Default")
      (node (ref "JP17") (pin "1") (pinfunction "1_1") (pintype "passive"))
      (node (ref "LED2") (pin "A") (pinfunction "A_A") (pintype "passive"))
      (node (ref "U3") (pin "P$16") (pinfunction "STEP_P$16") (pintype "input"))
    )
    (net (code "33") (name "/STP4") (class "Default")
      (node (ref "JP18") (pin "1") (pinfunction "1_1") (pintype "passive"))
      (node (ref "LED3") (pin "A") (pinfunction "A_A") (pintype "passive"))
      (node (ref "U4") (pin "P$16") (pinfunction "STEP_P$16") (pintype "input"))
    )
    (net (code "34") (name "GND") (class "Default")
      (node (ref "C1") (pin "2") (pinfunction "2_2") (pintype "passive"))
      (node (ref "C10") (pin "2") (pinfunction "2_2") (pintype "passive"))
      (node (ref "C11") (pin "2") (pinfunction "2_2") (pintype "passive"))
      (node (ref "C14") (pin "2") (pinfunction "2_2") (pintype "passive"))
      (node (ref "C15") (pin "2") (pinfunction "2_2") (pintype "passive"))
      (node (ref "C16") (pin "2") (pinfunction "2_2") (pintype "passive"))
      (node (ref "C17") (pin "2") (pinfunction "2_2") (pintype "passive"))
      (node (ref "C2") (pin "-") (pinfunction "-_-") (pintype "passive"))
      (node (ref "C20") (pin "2") (pinfunction "2_2") (pintype "passive"))
      (node (ref "C21") (pin "2") (pinfunction "2_2") (pintype "passive"))
      (node (ref "C22") (pin "2") (pinfunction "2_2") (pintype "passive"))
      (node (ref "C23") (pin "2") (pinfunction "2_2") (pintype "passive"))
      (node (ref "C26") (pin "2") (pinfunction "2_2") (pintype "passive"))
      (node (ref "C27") (pin "2") (pinfunction "2_2") (pintype "passive"))
      (node (ref "C28") (pin "2") (pinfunction "2_2") (pintype "passive"))
      (node (ref "C29") (pin "2") (pinfunction "2_2") (pintype "passive"))
      (node (ref "C3") (pin "C") (pinfunction "-_C") (pintype "passive"))
      (node (ref "C4") (pin "2") (pinfunction "2_2") (pintype "passive"))
      (node (ref "C5") (pin "2") (pinfunction "2_2") (pintype "passive"))
      (node (ref "C8") (pin "2") (pinfunction "2_2") (pintype "passive"))
      (node (ref "C9") (pin "2") (pinfunction "2_2") (pintype "passive"))
      (node (ref "JP21") (pin "2") (pinfunction "2_2") (pintype "passive"))
      (node (ref "JP22") (pin "1") (pinfunction "1_1") (pintype "passive"))
      (node (ref "JP22") (pin "2") (pinfunction "2_2") (pintype "passive"))
      (node (ref "JP22") (pin "3") (pinfunction "3_3") (pintype "passive"))
      (node (ref "JP22") (pin "4") (pinfunction "4_4") (pintype "passive"))
      (node (ref "JP27") (pin "1") (pinfunction "1_1") (pintype "passive"))
      (node (ref "JP30") (pin "1") (pinfunction "1_1") (pintype "passive"))
      (node (ref "JP30") (pin "2") (pinfunction "2_2") (pintype "passive"))
      (node (ref "JP30") (pin "3") (pinfunction "3_3") (pintype "passive"))
      (node (ref "JP30") (pin "4") (pinfunction "4_4") (pintype "passive"))
      (node (ref "JP31") (pin "1") (pinfunction "1_1") (pintype "passive"))
      (node (ref "JP31") (pin "2") (pinfunction "2_2") (pintype "passive"))
      (node (ref "JP31") (pin "3") (pinfunction "3_3") (pintype "passive"))
      (node (ref "JP31") (pin "4") (pinfunction "4_4") (pintype "passive"))
      (node (ref "JP32") (pin "1") (pinfunction "1_1") (pintype "passive"))
      (node (ref "JP32") (pin "2") (pinfunction "2_2") (pintype "passive"))
      (node (ref "JP32") (pin "3") (pinfunction "3_3") (pintype "passive"))
      (node (ref "JP32") (pin "4") (pinfunction "4_4") (pintype "passive"))
      (node (ref "JP33") (pin "1") (pinfunction "1_1") (pintype "passive"))
      (node (ref "JP33") (pin "2") (pinfunction "2_2") (pintype "passive"))
      (node (ref "JP33") (pin "3") (pinfunction "3_3") (pintype "passive"))
      (node (ref "R10") (pin "1") (pinfunction "CCW_1") (pintype "passive"))
      (node (ref "R11") (pin "1") (pinfunction "1_1") (pintype "passive"))
      (node (ref "R12") (pin "1") (pinfunction "1_1") (pintype "passive"))
      (node (ref "R13") (pin "2") (pinfunction "2_2") (pintype "passive"))
      (node (ref "R14") (pin "2") (pinfunction "2_2") (pintype "passive"))
      (node (ref "R17") (pin "1") (pinfunction "CCW_1") (pintype "passive"))
      (node (ref "R18") (pin "1") (pinfunction "1_1") (pintype "passive"))
      (node (ref "R19") (pin "1") (pinfunction "1_1") (pintype "passive"))
      (node (ref "R20") (pin "2") (pinfunction "2_2") (pintype "passive"))
      (node (ref "R21") (pin "2") (pinfunction "2_2") (pintype "passive"))
      (node (ref "R24") (pin "1") (pinfunction "CCW_1") (pintype "passive"))
      (node (ref "R25") (pin "1") (pinfunction "1_1") (pintype "passive"))
      (node (ref "R26") (pin "1") (pinfunction "1_1") (pintype "passive"))
      (node (ref "R27") (pin "2") (pinfunction "2_2") (pintype "passive"))
      (node (ref "R28") (pin "2") (pinfunction "2_2") (pintype "passive"))
      (node (ref "R3") (pin "1") (pinfunction "CCW_1") (pintype "passive"))
      (node (ref "R35") (pin "1") (pinfunction "1_1") (pintype "passive"))
      (node (ref "R36") (pin "1") (pinfunction "1_1") (pintype "passive"))
      (node (ref "R4") (pin "1") (pinfunction "1_1") (pintype "passive"))
      (node (ref "R5") (pin "1") (pinfunction "1_1") (pintype "passive"))
      (node (ref "R6") (pin "2") (pinfunction "2_2") (pintype "passive"))
      (node (ref "R7") (pin "2") (pinfunction "2_2") (pintype "passive"))
      (node (ref "SJ1") (pin "2") (pinfunction "2_2") (pintype "passive"))
      (node (ref "U1") (pin "P$18") (pinfunction "GND_P$18") (pintype "power_in"))
      (node (ref "U1") (pin "P$29") (pinfunction "GND_PAD_P$29") (pintype "power_in"))
      (node (ref "U1") (pin "P$3") (pinfunction "GND_P$3") (pintype "power_in"))
      (node (ref "U3") (pin "P$18") (pinfunction "GND_P$18") (pintype "power_in"))
      (node (ref "U3") (pin "P$29") (pinfunction "GND_PAD_P$29") (pintype "power_in"))
      (node (ref "U3") (pin "P$3") (pinfunction "GND_P$3") (pintype "power_in"))
      (node (ref "U4") (pin "P$18") (pinfunction "GND_P$18") (pintype "power_in"))
      (node (ref "U4") (pin "P$29") (pinfunction "GND_PAD_P$29") (pintype "power_in"))
      (node (ref "U4") (pin "P$3") (pinfunction "GND_P$3") (pintype "power_in"))
      (node (ref "U5") (pin "P$18") (pinfunction "GND_P$18") (pintype "power_in"))
      (node (ref "U5") (pin "P$29") (pinfunction "GND_PAD_P$29") (pintype "power_in"))
      (node (ref "U5") (pin "P$3") (pinfunction "GND_P$3") (pintype "power_in"))
    )
    (net (code "35") (name "Net-(LED1-PadC)") (class "Default")
      (node (ref "LED1") (pin "C") (pinfunction "C_C") (pintype "passive"))
      (node (ref "R7") (pin "1") (pinfunction "1_1") (pintype "passive"))
    )
    (net (code "36") (name "Net-(LED2-PadC)") (class "Default")
      (node (ref "LED2") (pin "C") (pinfunction "C_C") (pintype "passive"))
      (node (ref "R14") (pin "1") (pinfunction "1_1") (pintype "passive"))
    )
    (net (code "37") (name "Net-(LED3-PadC)") (class "Default")
      (node (ref "LED3") (pin "C") (pinfunction "C_C") (pintype "passive"))
      (node (ref "R21") (pin "1") (pinfunction "1_1") (pintype "passive"))
    )
    (net (code "38") (name "Net-(LED4-PadC)") (class "Default")
      (node (ref "LED4") (pin "C") (pinfunction "C_C") (pintype "passive"))
      (node (ref "R28") (pin "1") (pinfunction "1_1") (pintype "passive"))
    )
    (net (code "39") (name "Net-(LED5-PadC)") (class "Default")
      (node (ref "LED5") (pin "C") (pinfunction "C_C") (pintype "passive"))
      (node (ref "R36") (pin "2") (pinfunction "2_2") (pintype "passive"))
    )
    (net (code "40") (name "Net-(R2-Pad1)") (class "Default")
      (node (ref "R2") (pin "1") (pinfunction "1_1") (pintype "passive"))
      (node (ref "R35") (pin "2") (pinfunction "2_2") (pintype "passive"))
      (node (ref "SJ1") (pin "1") (pinfunction "1_1") (pintype "passive"))
    )
    (net (code "41") (name "Net-(R3-CW)") (class "Default")
      (node (ref "R3") (pin "3") (pinfunction "CW_3") (pintype "passive"))
      (node (ref "R52") (pin "1") (pinfunction "1_1") (pintype "passive"))
    )
    (net (code "42") (name "Net-(R3-WIPER)") (class "Default")
      (node (ref "R3") (pin "2") (pinfunction "WIPER_2") (pintype "passive"))
      (node (ref "TP1") (pin "P$1") (pinfunction "1_P$1") (pintype "bidirectional"))
      (node (ref "U1") (pin "P$17") (pinfunction "REF_P$17") (pintype "bidirectional"))
    )
    (net (code "43") (name "Net-(R10-CW)") (class "Default")
      (node (ref "R10") (pin "3") (pinfunction "CW_3") (pintype "passive"))
      (node (ref "R49") (pin "1") (pinfunction "1_1") (pintype "passive"))
    )
    (net (code "44") (name "Net-(R10-WIPER)") (class "Default")
      (node (ref "R10") (pin "2") (pinfunction "WIPER_2") (pintype "passive"))
      (node (ref "TP4") (pin "P$1") (pinfunction "1_P$1") (pintype "bidirectional"))
      (node (ref "U3") (pin "P$17") (pinfunction "REF_P$17") (pintype "bidirectional"))
    )
    (net (code "45") (name "Net-(R17-CW)") (class "Default")
      (node (ref "R17") (pin "3") (pinfunction "CW_3") (pintype "passive"))
      (node (ref "R50") (pin "1") (pinfunction "1_1") (pintype "passive"))
    )
    (net (code "46") (name "Net-(R17-WIPER)") (class "Default")
      (node (ref "R17") (pin "2") (pinfunction "WIPER_2") (pintype "passive"))
      (node (ref "TP3") (pin "P$1") (pinfunction "1_P$1") (pintype "bidirectional"))
      (node (ref "U4") (pin "P$17") (pinfunction "REF_P$17") (pintype "bidirectional"))
    )
    (net (code "47") (name "Net-(R24-CW)") (class "Default")
      (node (ref "R24") (pin "3") (pinfunction "CW_3") (pintype "passive"))
      (node (ref "R51") (pin "1") (pinfunction "1_1") (pintype "passive"))
    )
    (net (code "48") (name "Net-(R24-WIPER)") (class "Default")
      (node (ref "R24") (pin "2") (pinfunction "WIPER_2") (pintype "passive"))
      (node (ref "TP2") (pin "P$1") (pinfunction "1_P$1") (pintype "bidirectional"))
      (node (ref "U5") (pin "P$17") (pinfunction "REF_P$17") (pintype "bidirectional"))
    )
    (net (code "49") (name "Net-(U1-CP1)") (class "Default")
      (node (ref "C6") (pin "1") (pinfunction "1_1") (pintype "passive"))
      (node (ref "U1") (pin "P$4") (pinfunction "CP1_P$4") (pintype "bidirectional"))
    )
    (net (code "50") (name "Net-(U1-CP2)") (class "Default")
      (node (ref "C6") (pin "2") (pinfunction "2_2") (pintype "passive"))
      (node (ref "U1") (pin "P$5") (pinfunction "CP2_P$5") (pintype "bidirectional"))
    )
    (net (code "51") (name "Net-(U1-OUT1A)") (class "Default")
      (node (ref "JP1") (pin "2") (pinfunction "2_2") (pintype "passive"))
      (node (ref "JP29") (pin "2") (pinfunction "2_2") (pintype "passive"))
      (node (ref "U1") (pin "P$24") (pinfunction "OUT1A_P$24") (pintype "bidirectional"))
    )
    (net (code "52") (name "Net-(U1-OUT1B)") (class "Default")
      (node (ref "JP1") (pin "1") (pinfunction "1_1") (pintype "passive"))
      (node (ref "JP29") (pin "1") (pinfunction "1_1") (pintype "passive"))
      (node (ref "U1") (pin "P$21") (pinfunction "OUT1B_P$21") (pintype "bidirectional"))
    )
    (net (code "53") (name "Net-(U1-OUT2A)") (class "Default")
      (node (ref "JP2") (pin "1") (pinfunction "1_1") (pintype "passive"))
      (node (ref "JP29") (pin "3") (pinfunction "3_3") (pintype "passive"))
      (node (ref "U1") (pin "P$26") (pinfunction "OUT2A_P$26") (pintype "bidirectional"))
    )
    (net (code "54") (name "Net-(U1-OUT2B)") (class "Default")
      (node (ref "JP2") (pin "2") (pinfunction "2_2") (pintype "passive"))
      (node (ref "JP29") (pin "4") (pinfunction "4_4") (pintype "passive"))
      (node (ref "U1") (pin "P$1") (pinfunction "OUT2B_P$1") (pintype "bidirectional"))
    )
    (net (code "55") (name "Net-(U1-ROSC)") (class "Default")
      (node (ref "R6") (pin "1") (pinfunction "1_1") (pintype "passive"))
      (node (ref "U1") (pin "P$13") (pinfunction "ROSC_P$13") (pintype "bidirectional"))
    )
    (net (code "56") (name "Net-(U1-SENSE1)") (class "Default")
      (node (ref "R4") (pin "2") (pinfunction "2_2") (pintype "passive"))
      (node (ref "U1") (pin "P$23") (pinfunction "SENSE1_P$23") (pintype "bidirectional"))
    )
    (net (code "57") (name "Net-(U1-SENSE2)") (class "Default")
      (node (ref "R5") (pin "2") (pinfunction "2_2") (pintype "passive"))
      (node (ref "U1") (pin "P$27") (pinfunction "SENSE2_P$27") (pintype "bidirectional"))
    )
    (net (code "58") (name "Net-(U1-VCP)") (class "Default")
      (node (ref "C7") (pin "1") (pinfunction "1_1") (pintype "passive"))
      (node (ref "U1") (pin "P$6") (pinfunction "VCP_P$6") (pintype "bidirectional"))
    )
    (net (code "59") (name "Net-(U1-VREG)") (class "Default")
      (node (ref "C8") (pin "1") (pinfunction "1_1") (pintype "passive"))
      (node (ref "U1") (pin "P$8") (pinfunction "VREG_P$8") (pintype "bidirectional"))
    )
    (net (code "60") (name "Net-(U2-GND)") (class "Default")
      (node (ref "R1") (pin "1") (pinfunction "1_1") (pintype "passive"))
      (node (ref "R2") (pin "2") (pinfunction "2_2") (pintype "passive"))
      (node (ref "U2") (pin "1") (pinfunction "GND_1") (pintype "input"))
    )
    (net (code "61") (name "Net-(U2-IN)") (class "Default")
      (node (ref "C5") (pin "1") (pinfunction "1_1") (pintype "passive"))
      (node (ref "F1") (pin "2") (pinfunction "2_2") (pintype "bidirectional"))
      (node (ref "U2") (pin "3") (pinfunction "IN_3") (pintype "input"))
    )
    (net (code "62") (name "Net-(U3-CP1)") (class "Default")
      (node (ref "C12") (pin "1") (pinfunction "1_1") (pintype "passive"))
      (node (ref "U3") (pin "P$4") (pinfunction "CP1_P$4") (pintype "bidirectional"))
    )
    (net (code "63") (name "Net-(U3-CP2)") (class "Default")
      (node (ref "C12") (pin "2") (pinfunction "2_2") (pintype "passive"))
      (node (ref "U3") (pin "P$5") (pinfunction "CP2_P$5") (pintype "bidirectional"))
    )
    (net (code "64") (name "Net-(U3-OUT1A)") (class "Default")
      (node (ref "JP26") (pin "2") (pinfunction "2_2") (pintype "passive"))
      (node (ref "JP5") (pin "2") (pinfunction "2_2") (pintype "passive"))
      (node (ref "U3") (pin "P$24") (pinfunction "OUT1A_P$24") (pintype "bidirectional"))
    )
    (net (code "65") (name "Net-(U3-OUT1B)") (class "Default")
      (node (ref "JP26") (pin "1") (pinfunction "1_1") (pintype "passive"))
      (node (ref "JP5") (pin "1") (pinfunction "1_1") (pintype "passive"))
      (node (ref "U3") (pin "P$21") (pinfunction "OUT1B_P$21") (pintype "bidirectional"))
    )
    (net (code "66") (name "Net-(U3-OUT2A)") (class "Default")
      (node (ref "JP26") (pin "3") (pinfunction "3_3") (pintype "passive"))
      (node (ref "JP6") (pin "1") (pinfunction "1_1") (pintype "passive"))
      (node (ref "U3") (pin "P$26") (pinfunction "OUT2A_P$26") (pintype "bidirectional"))
    )
    (net (code "67") (name "Net-(U3-OUT2B)") (class "Default")
      (node (ref "JP26") (pin "4") (pinfunction "4_4") (pintype "passive"))
      (node (ref "JP6") (pin "2") (pinfunction "2_2") (pintype "passive"))
      (node (ref "U3") (pin "P$1") (pinfunction "OUT2B_P$1") (pintype "bidirectional"))
    )
    (net (code "68") (name "Net-(U3-ROSC)") (class "Default")
      (node (ref "R13") (pin "1") (pinfunction "1_1") (pintype "passive"))
      (node (ref "U3") (pin "P$13") (pinfunction "ROSC_P$13") (pintype "bidirectional"))
    )
    (net (code "69") (name "Net-(U3-SENSE1)") (class "Default")
      (node (ref "R11") (pin "2") (pinfunction "2_2") (pintype "passive"))
      (node (ref "U3") (pin "P$23") (pinfunction "SENSE1_P$23") (pintype "bidirectional"))
    )
    (net (code "70") (name "Net-(U3-SENSE2)") (class "Default")
      (node (ref "R12") (pin "2") (pinfunction "2_2") (pintype "passive"))
      (node (ref "U3") (pin "P$27") (pinfunction "SENSE2_P$27") (pintype "bidirectional"))
    )
    (net (code "71") (name "Net-(U3-VCP)") (class "Default")
      (node (ref "C13") (pin "1") (pinfunction "1_1") (pintype "passive"))
      (node (ref "U3") (pin "P$6") (pinfunction "VCP_P$6") (pintype "bidirectional"))
    )
    (net (code "72") (name "Net-(U3-VREG)") (class "Default")
      (node (ref "C14") (pin "1") (pinfunction "1_1") (pintype "passive"))
      (node (ref "U3") (pin "P$8") (pinfunction "VREG_P$8") (pintype "bidirectional"))
    )
    (net (code "73") (name "Net-(U4-CP1)") (class "Default")
      (node (ref "C18") (pin "1") (pinfunction "1_1") (pintype "passive"))
      (node (ref "U4") (pin "P$4") (pinfunction "CP1_P$4") (pintype "bidirectional"))
    )
    (net (code "74") (name "Net-(U4-CP2)") (class "Default")
      (node (ref "C18") (pin "2") (pinfunction "2_2") (pintype "passive"))
      (node (ref "U4") (pin "P$5") (pinfunction "CP2_P$5") (pintype "bidirectional"))
    )
    (net (code "75") (name "Net-(U4-OUT1A)") (class "Default")
      (node (ref "JP13") (pin "2") (pinfunction "2_2") (pintype "passive"))
      (node (ref "JP7") (pin "2") (pinfunction "2_2") (pintype "passive"))
      (node (ref "U4") (pin "P$24") (pinfunction "OUT1A_P$24") (pintype "bidirectional"))
    )
    (net (code "76") (name "Net-(U4-OUT1B)") (class "Default")
      (node (ref "JP13") (pin "1") (pinfunction "1_1") (pintype "passive"))
      (node (ref "JP7") (pin "1") (pinfunction "1_1") (pintype "passive"))
      (node (ref "U4") (pin "P$21") (pinfunction "OUT1B_P$21") (pintype "bidirectional"))
    )
    (net (code "77") (name "Net-(U4-OUT2A)") (class "Default")
      (node (ref "JP13") (pin "3") (pinfunction "3_3") (pintype "passive"))
      (node (ref "JP8") (pin "1") (pinfunction "1_1") (pintype "passive"))
      (node (ref "U4") (pin "P$26") (pinfunction "OUT2A_P$26") (pintype "bidirectional"))
    )
    (net (code "78") (name "Net-(U4-OUT2B)") (class "Default")
      (node (ref "JP13") (pin "4") (pinfunction "4_4") (pintype "passive"))
      (node (ref "JP8") (pin "2") (pinfunction "2_2") (pintype "passive"))
      (node (ref "U4") (pin "P$1") (pinfunction "OUT2B_P$1") (pintype "bidirectional"))
    )
    (net (code "79") (name "Net-(U4-ROSC)") (class "Default")
      (node (ref "R20") (pin "1") (pinfunction "1_1") (pintype "passive"))
      (node (ref "U4") (pin "P$13") (pinfunction "ROSC_P$13") (pintype "bidirectional"))
    )
    (net (code "80") (name "Net-(U4-SENSE1)") (class "Default")
      (node (ref "R18") (pin "2") (pinfunction "2_2") (pintype "passive"))
      (node (ref "U4") (pin "P$23") (pinfunction "SENSE1_P$23") (pintype "bidirectional"))
    )
    (net (code "81") (name "Net-(U4-SENSE2)") (class "Default")
      (node (ref "R19") (pin "2") (pinfunction "2_2") (pintype "passive"))
      (node (ref "U4") (pin "P$27") (pinfunction "SENSE2_P$27") (pintype "bidirectional"))
    )
    (net (code "82") (name "Net-(U4-VCP)") (class "Default")
      (node (ref "C19") (pin "1") (pinfunction "1_1") (pintype "passive"))
      (node (ref "U4") (pin "P$6") (pinfunction "VCP_P$6") (pintype "bidirectional"))
    )
    (net (code "83") (name "Net-(U4-VREG)") (class "Default")
      (node (ref "C20") (pin "1") (pinfunction "1_1") (pintype "passive"))
      (node (ref "U4") (pin "P$8") (pinfunction "VREG_P$8") (pintype "bidirectional"))
    )
    (net (code "84") (name "Net-(U5-CP1)") (class "Default")
      (node (ref "C24") (pin "1") (pinfunction "1_1") (pintype "passive"))
      (node (ref "U5") (pin "P$4") (pinfunction "CP1_P$4") (pintype "bidirectional"))
    )
    (net (code "85") (name "Net-(U5-CP2)") (class "Default")
      (node (ref "C24") (pin "2") (pinfunction "2_2") (pintype "passive"))
      (node (ref "U5") (pin "P$5") (pinfunction "CP2_P$5") (pintype "bidirectional"))
    )
    (net (code "86") (name "Net-(U5-OUT1A)") (class "Default")
      (node (ref "JP14") (pin "2") (pinfunction "2_2") (pintype "passive"))
      (node (ref "JP28") (pin "2") (pinfunction "2_2") (pintype "passive"))
      (node (ref "U5") (pin "P$24") (pinfunction "OUT1A_P$24") (pintype "bidirectional"))
    )
    (net (code "87") (name "Net-(U5-OUT1B)") (class "Default")
      (node (ref "JP14") (pin "1") (pinfunction "1_1") (pintype "passive"))
      (node (ref "JP28") (pin "1") (pinfunction "1_1") (pintype "passive"))
      (node (ref "U5") (pin "P$21") (pinfunction "OUT1B_P$21") (pintype "bidirectional"))
    )
    (net (code "88") (name "Net-(U5-OUT2A)") (class "Default")
      (node (ref "JP15") (pin "1") (pinfunction "1_1") (pintype "passive"))
      (node (ref "JP28") (pin "3") (pinfunction "3_3") (pintype "passive"))
      (node (ref "U5") (pin "P$26") (pinfunction "OUT2A_P$26") (pintype "bidirectional"))
    )
    (net (code "89") (name "Net-(U5-OUT2B)") (class "Default")
      (node (ref "JP15") (pin "2") (pinfunction "2_2") (pintype "passive"))
      (node (ref "JP28") (pin "4") (pinfunction "4_4") (pintype "passive"))
      (node (ref "U5") (pin "P$1") (pinfunction "OUT2B_P$1") (pintype "bidirectional"))
    )
    (net (code "90") (name "Net-(U5-ROSC)") (class "Default")
      (node (ref "R27") (pin "1") (pinfunction "1_1") (pintype "passive"))
      (node (ref "U5") (pin "P$13") (pinfunction "ROSC_P$13") (pintype "bidirectional"))
    )
    (net (code "91") (name "Net-(U5-SENSE1)") (class "Default")
      (node (ref "R25") (pin "2") (pinfunction "2_2") (pintype "passive"))
      (node (ref "U5") (pin "P$23") (pinfunction "SENSE1_P$23") (pintype "bidirectional"))
    )
    (net (code "92") (name "Net-(U5-SENSE2)") (class "Default")
      (node (ref "R26") (pin "2") (pinfunction "2_2") (pintype "passive"))
      (node (ref "U5") (pin "P$27") (pinfunction "SENSE2_P$27") (pintype "bidirectional"))
    )
    (net (code "93") (name "Net-(U5-VCP)") (class "Default")
      (node (ref "C25") (pin "1") (pinfunction "1_1") (pintype "passive"))
      (node (ref "U5") (pin "P$6") (pinfunction "VCP_P$6") (pintype "bidirectional"))
    )
    (net (code "94") (name "Net-(U5-VREG)") (class "Default")
      (node (ref "C26") (pin "1") (pinfunction "1_1") (pintype "passive"))
      (node (ref "U5") (pin "P$8") (pinfunction "VREG_P$8") (pintype "bidirectional"))
    )
    (net (code "95") (name "VCC") (class "Default")
      (node (ref "C1") (pin "1") (pinfunction "1_1") (pintype "passive"))
      (node (ref "C15") (pin "1") (pinfunction "1_1") (pintype "passive"))
      (node (ref "C21") (pin "1") (pinfunction "1_1") (pintype "passive"))
      (node (ref "C27") (pin "1") (pinfunction "1_1") (pintype "passive"))
      (node (ref "C3") (pin "A") (pinfunction "+_A") (pintype "passive"))
      (node (ref "C4") (pin "1") (pinfunction "1_1") (pintype "passive"))
      (node (ref "C9") (pin "1") (pinfunction "1_1") (pintype "passive"))
      (node (ref "JP34") (pin "1") (pinfunction "1_1") (pintype "passive"))
      (node (ref "JP34") (pin "2") (pinfunction "2_2") (pintype "passive"))
      (node (ref "JP34") (pin "3") (pinfunction "3_3") (pintype "passive"))
      (node (ref "LED5") (pin "A") (pinfunction "A_A") (pintype "passive"))
      (node (ref "R1") (pin "2") (pinfunction "2_2") (pintype "passive"))
      (node (ref "R15") (pin "1") (pinfunction "1_1") (pintype "passive"))
      (node (ref "R16") (pin "1") (pinfunction "1_1") (pintype "passive"))
      (node (ref "R22") (pin "1") (pinfunction "1_1") (pintype "passive"))
      (node (ref "R23") (pin "1") (pinfunction "1_1") (pintype "passive"))
      (node (ref "R29") (pin "1") (pinfunction "1_1") (pintype "passive"))
      (node (ref "R30") (pin "1") (pinfunction "1_1") (pintype "passive"))
      (node (ref "R31") (pin "1") (pinfunction "1_1") (pintype "passive"))
      (node (ref "R32") (pin "1") (pinfunction "1_1") (pintype "passive"))
      (node (ref "R33") (pin "1") (pinfunction "1_1") (pintype "passive"))
      (node (ref "R34") (pin "1") (pinfunction "1_1") (pintype "passive"))
      (node (ref "R37") (pin "1") (pinfunction "1_1") (pintype "passive"))
      (node (ref "R38") (pin "1") (pinfunction "1_1") (pintype "passive"))
      (node (ref "R39") (pin "1") (pinfunction "1_1") (pintype "passive"))
      (node (ref "R40") (pin "1") (pinfunction "1_1") (pintype "passive"))
      (node (ref "R41") (pin "1") (pinfunction "1_1") (pintype "passive"))
      (node (ref "R42") (pin "1") (pinfunction "1_1") (pintype "passive"))
      (node (ref "R43") (pin "1") (pinfunction "1_1") (pintype "passive"))
      (node (ref "R44") (pin "1") (pinfunction "1_1") (pintype "passive"))
      (node (ref "R45") (pin "1") (pinfunction "1_1") (pintype "passive"))
      (node (ref "R46") (pin "1") (pinfunction "1_1") (pintype "passive"))
      (node (ref "R47") (pin "1") (pinfunction "1_1") (pintype "passive"))
      (node (ref "R48") (pin "1") (pinfunction "1_1") (pintype "passive"))
      (node (ref "R49") (pin "2") (pinfunction "2_2") (pintype "passive"))
      (node (ref "R50") (pin "2") (pinfunction "2_2") (pintype "passive"))
      (node (ref "R51") (pin "2") (pinfunction "2_2") (pintype "passive"))
      (node (ref "R52") (pin "2") (pinfunction "2_2") (pintype "passive"))
      (node (ref "R8") (pin "1") (pinfunction "1_1") (pintype "passive"))
      (node (ref "R9") (pin "1") (pinfunction "1_1") (pintype "passive"))
      (node (ref "U1") (pin "P$15") (pinfunction "VDD_P$15") (pintype "power_in"))
      (node (ref "U2") (pin "4") (pinfunction "OUT_4") (pintype "output"))
      (node (ref "U3") (pin "P$15") (pinfunction "VDD_P$15") (pintype "power_in"))
      (node (ref "U4") (pin "P$15") (pinfunction "VDD_P$15") (pintype "power_in"))
      (node (ref "U5") (pin "P$15") (pinfunction "VDD_P$15") (pintype "power_in"))
    )
    (net (code "96") (name "VIN") (class "Default")
      (node (ref "C10") (pin "1") (pinfunction "1_1") (pintype "passive"))
      (node (ref "C11") (pin "1") (pinfunction "1_1") (pintype "passive"))
      (node (ref "C13") (pin "2") (pinfunction "2_2") (pintype "passive"))
      (node (ref "C16") (pin "1") (pinfunction "1_1") (pintype "passive"))
      (node (ref "C17") (pin "1") (pinfunction "1_1") (pintype "passive"))
      (node (ref "C19") (pin "2") (pinfunction "2_2") (pintype "passive"))
      (node (ref "C2") (pin "+") (pinfunction "+_+") (pintype "passive"))
      (node (ref "C22") (pin "1") (pinfunction "1_1") (pintype "passive"))
      (node (ref "C23") (pin "1") (pinfunction "1_1") (pintype "passive"))
      (node (ref "C25") (pin "2") (pinfunction "2_2") (pintype "passive"))
      (node (ref "C28") (pin "1") (pinfunction "1_1") (pintype "passive"))
      (node (ref "C29") (pin "1") (pinfunction "1_1") (pintype "passive"))
      (node (ref "C7") (pin "2") (pinfunction "2_2") (pintype "passive"))
      (node (ref "D1") (pin "C") (pinfunction "C_C") (pintype "passive"))
      (node (ref "F1") (pin "1") (pinfunction "1_1") (pintype "bidirectional"))
      (node (ref "U1") (pin "P$22") (pinfunction "VBB1_P$22") (pintype "bidirectional"))
      (node (ref "U1") (pin "P$28") (pinfunction "VBB2_P$28") (pintype "bidirectional"))
      (node (ref "U3") (pin "P$22") (pinfunction "VBB1_P$22") (pintype "bidirectional"))
      (node (ref "U3") (pin "P$28") (pinfunction "VBB2_P$28") (pintype "bidirectional"))
      (node (ref "U4") (pin "P$22") (pinfunction "VBB1_P$22") (pintype "bidirectional"))
      (node (ref "U4") (pin "P$28") (pinfunction "VBB2_P$28") (pintype "bidirectional"))
      (node (ref "U5") (pin "P$22") (pinfunction "VBB1_P$22") (pintype "bidirectional"))
      (node (ref "U5") (pin "P$28") (pinfunction "VBB2_P$28") (pintype "bidirectional"))
    )
    (net (code "97") (name "unconnected-(U1-NC-PadP$7)") (class "Default")
      (node (ref "U1") (pin "P$7") (pinfunction "NC_P$7") (pintype "no_connect"))
    )
    (net (code "98") (name "unconnected-(U1-NC-PadP$20)") (class "Default")
      (node (ref "U1") (pin "P$20") (pinfunction "NC_P$20") (pintype "no_connect"))
    )
    (net (code "99") (name "unconnected-(U1-NC-PadP$25)") (class "Default")
      (node (ref "U1") (pin "P$25") (pinfunction "NC_P$25") (pintype "no_connect"))
    )
    (net (code "100") (name "unconnected-(U3-NC-PadP$7)") (class "Default")
      (node (ref "U3") (pin "P$7") (pinfunction "NC_P$7") (pintype "no_connect"))
    )
    (net (code "101") (name "unconnected-(U3-NC-PadP$20)") (class "Default")
      (node (ref "U3") (pin "P$20") (pinfunction "NC_P$20") (pintype "no_connect"))
    )
    (net (code "102") (name "unconnected-(U3-NC-PadP$25)") (class "Default")
      (node (ref "U3") (pin "P$25") (pinfunction "NC_P$25") (pintype "no_connect"))
    )
    (net (code "103") (name "unconnected-(U4-NC-PadP$7)") (class "Default")
      (node (ref "U4") (pin "P$7") (pinfunction "NC_P$7") (pintype "no_connect"))
    )
    (net (code "104") (name "unconnected-(U4-NC-PadP$20)") (class "Default")
      (node (ref "U4") (pin "P$20") (pinfunction "NC_P$20") (pintype "no_connect"))
    )
    (net (code "105") (name "unconnected-(U4-NC-PadP$25)") (class "Default")
      (node (ref "U4") (pin "P$25") (pinfunction "NC_P$25") (pintype "no_connect"))
    )
    (net (code "106") (name "unconnected-(U5-NC-PadP$7)") (class "Default")
      (node (ref "U5") (pin "P$7") (pinfunction "NC_P$7") (pintype "no_connect"))
    )
    (net (code "107") (name "unconnected-(U5-NC-PadP$20)") (class "Default")
      (node (ref "U5") (pin "P$20") (pinfunction "NC_P$20") (pintype "no_connect"))
    )
    (net (code "108") (name "unconnected-(U5-NC-PadP$25)") (class "Default")
      (node (ref "U5") (pin "P$25") (pinfunction "NC_P$25") (pintype "no_connect"))
    )
  )
)
